# bridge.net
KiCad netlist of a schematic drawn in Altium Designer
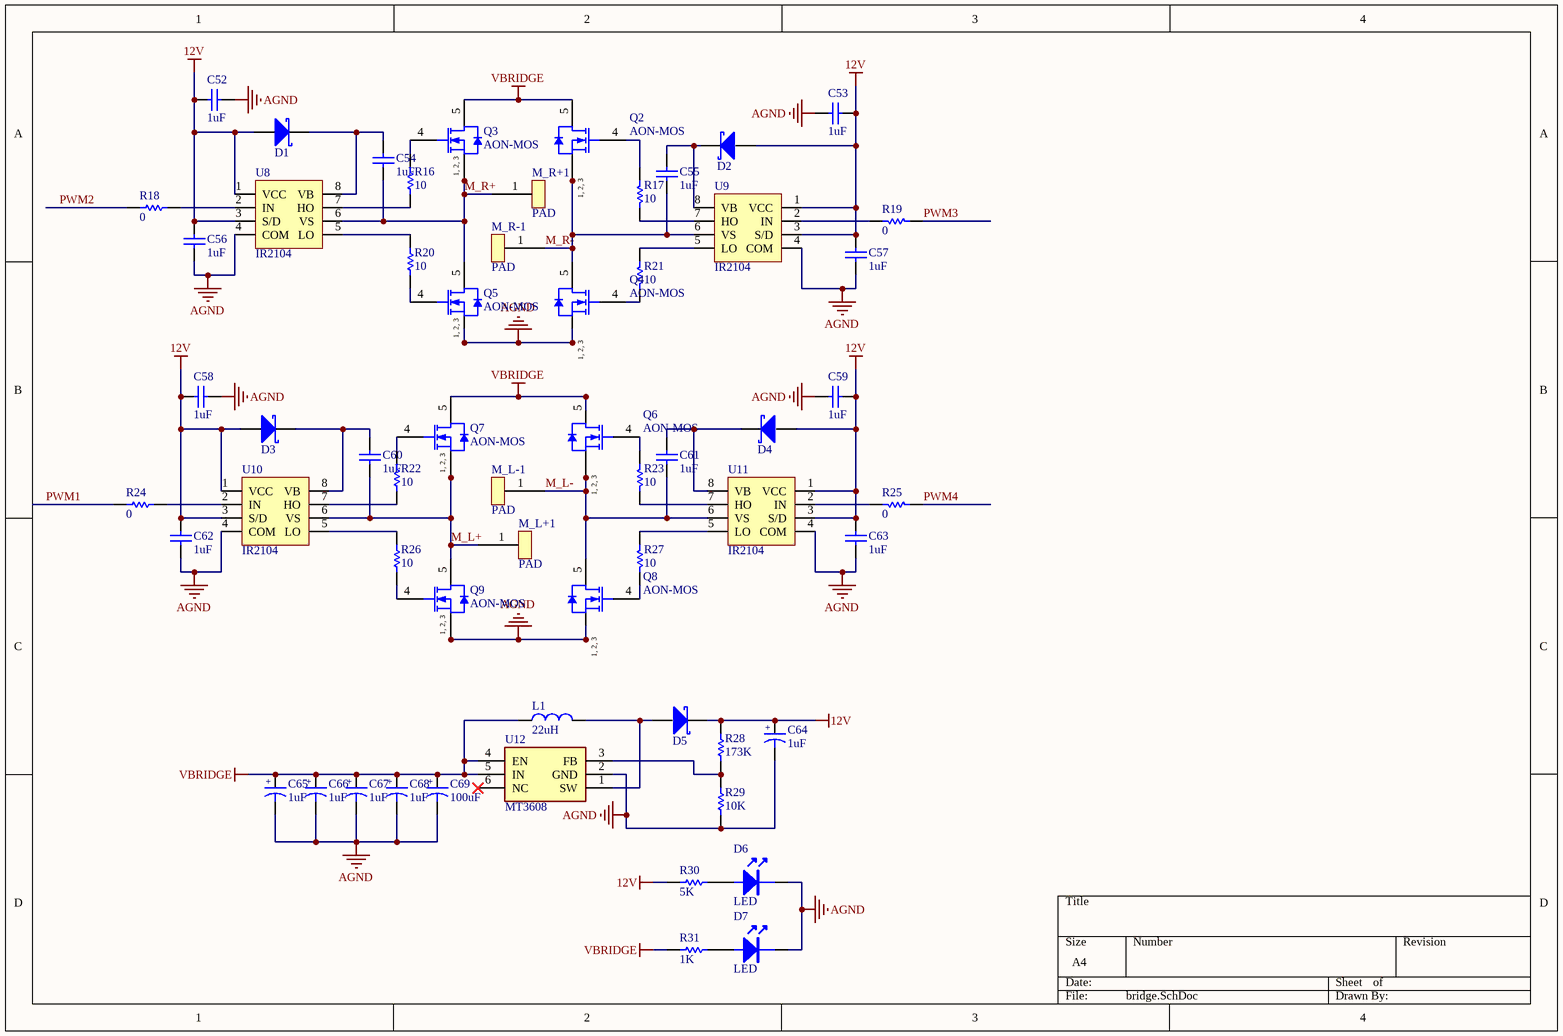
[diagram p0: bridge.SchDoc]

(export (version "E")
  (design (tool "Eeschema 10.0.6"))
  (components
    (comp (ref "C52")
      (value "1uF")
      (footprint "C1210")
      (description "Capacitor")
      (fields (field (name "PUBLISHER") "Altium Limited"))
      (libsource (lib "My Footprint") (part "CAP"))
    )
    (comp (ref "C53")
      (value "1uF")
      (footprint "C1210")
      (description "Capacitor")
      (fields (field (name "PUBLISHER") "Altium Limited"))
      (libsource (lib "My Footprint") (part "CAP"))
    )
    (comp (ref "C54")
      (value "1uF")
      (footprint "0603_C")
      (description "Capacitor")
      (fields (field (name "PUBLISHER") "Altium Limited"))
      (libsource (lib "My Footprint") (part "CAP"))
    )
    (comp (ref "C55")
      (value "1uF")
      (footprint "0603_C")
      (description "Capacitor")
      (fields (field (name "PUBLISHER") "Altium Limited"))
      (libsource (lib "My Footprint") (part "CAP"))
    )
    (comp (ref "C56")
      (value "1uF")
      (footprint "0603_C")
      (description "Capacitor")
      (fields (field (name "PUBLISHER") "Altium Limited"))
      (libsource (lib "My Footprint") (part "CAP"))
    )
    (comp (ref "C57")
      (value "1uF")
      (footprint "0603_C")
      (description "Capacitor")
      (fields (field (name "PUBLISHER") "Altium Limited"))
      (libsource (lib "My Footprint") (part "CAP"))
    )
    (comp (ref "C58")
      (value "1uF")
      (footprint "C1210")
      (description "Capacitor")
      (fields (field (name "PUBLISHER") "Altium Limited"))
      (libsource (lib "My Footprint") (part "CAP"))
    )
    (comp (ref "C59")
      (value "1uF")
      (footprint "C1210")
      (description "Capacitor")
      (fields (field (name "PUBLISHER") "Altium Limited"))
      (libsource (lib "My Footprint") (part "CAP"))
    )
    (comp (ref "C60")
      (value "1uF")
      (footprint "0603_C")
      (description "Capacitor")
      (fields (field (name "PUBLISHER") "Altium Limited"))
      (libsource (lib "My Footprint") (part "CAP"))
    )
    (comp (ref "C61")
      (value "1uF")
      (footprint "0603_C")
      (description "Capacitor")
      (fields (field (name "PUBLISHER") "Altium Limited"))
      (libsource (lib "My Footprint") (part "CAP"))
    )
    (comp (ref "C62")
      (value "1uF")
      (footprint "0603_C")
      (description "Capacitor")
      (fields (field (name "PUBLISHER") "Altium Limited"))
      (libsource (lib "My Footprint") (part "CAP"))
    )
    (comp (ref "C63")
      (value "1uF")
      (footprint "0603_C")
      (description "Capacitor")
      (fields (field (name "PUBLISHER") "Altium Limited"))
      (libsource (lib "My Footprint") (part "CAP"))
    )
    (comp (ref "C64") (value "1uF") (footprint "C6.3X6.3") (libsource (lib "My Footprint") (part "CAP1")))
    (comp (ref "C65") (value "1uF") (footprint "C6.3X6.3") (libsource (lib "My Footprint") (part "CAP1")))
    (comp (ref "C66") (value "1uF") (footprint "C6.3X6.3") (libsource (lib "My Footprint") (part "CAP1")))
    (comp (ref "C67") (value "1uF") (footprint "C6.3X6.3") (libsource (lib "My Footprint") (part "CAP1")))
    (comp (ref "C68") (value "1uF") (footprint "C6.3X6.3") (libsource (lib "My Footprint") (part "CAP1")))
    (comp (ref "C69")
      (value "100uF")
      (footprint "C6.3X6.3")
      (libsource (lib "PCB_Project1") (part "Cap_polar"))
    )
    (comp (ref "D1")
      (value "Diode Schottky")
      (footprint "DO-214AC")
      (libsource (lib "通用驱动") (part "Diode Schottky"))
    )
    (comp (ref "D2")
      (value "Diode Schottky")
      (footprint "DO-214AC")
      (libsource (lib "通用驱动") (part "Diode Schottky"))
    )
    (comp (ref "D3")
      (value "Diode Schottky")
      (footprint "DO-214AC")
      (libsource (lib "通用驱动") (part "Diode Schottky"))
    )
    (comp (ref "D4")
      (value "Diode Schottky")
      (footprint "DO-214AC")
      (libsource (lib "通用驱动") (part "Diode Schottky"))
    )
    (comp (ref "D5")
      (value "Diode Schottky")
      (footprint "DO-214AC")
      (libsource (lib "通用驱动") (part "Diode Schottky"))
    )
    (comp (ref "D6")
      (value "LED")
      (footprint "0603_LED")
      (description "LED 发光二极管")
      (libsource (lib "My Footprint") (part "LED"))
    )
    (comp (ref "D7")
      (value "LED")
      (footprint "0603_LED")
      (description "LED 发光二极管")
      (libsource (lib "My Footprint") (part "LED"))
    )
    (comp (ref "L1")
      (value "22uH")
      (footprint "L 5x5")
      (libsource (lib "My Footprint") (part "L_Inductance"))
    )
    (comp (ref "M_L+1") (value "PAD") (footprint "PAD_BIG") (libsource (lib "My Footprint") (part "PAD")))
    (comp (ref "M_L-1") (value "PAD") (footprint "PAD_BIG") (libsource (lib "") (part "PAD_1")))
    (comp (ref "M_R+1") (value "PAD") (footprint "PAD_BIG") (libsource (lib "My Footprint") (part "PAD")))
    (comp (ref "M_R-1") (value "PAD") (footprint "PAD_BIG") (libsource (lib "") (part "PAD_1")))
    (comp (ref "Q2") (value "AON-MOS") (footprint "so-8") (libsource (lib "My Footprint") (part "N-MOS-so")))
    (comp (ref "Q3") (value "AON-MOS") (footprint "so-8") (libsource (lib "My Footprint") (part "N-MOS-so")))
    (comp (ref "Q4") (value "AON-MOS") (footprint "so-8") (libsource (lib "My Footprint") (part "N-MOS-so")))
    (comp (ref "Q5") (value "AON-MOS") (footprint "so-8") (libsource (lib "My Footprint") (part "N-MOS-so")))
    (comp (ref "Q6") (value "AON-MOS") (footprint "so-8") (libsource (lib "My Footprint") (part "N-MOS-so")))
    (comp (ref "Q7") (value "AON-MOS") (footprint "so-8") (libsource (lib "My Footprint") (part "N-MOS-so")))
    (comp (ref "Q8") (value "AON-MOS") (footprint "so-8") (libsource (lib "My Footprint") (part "N-MOS-so")))
    (comp (ref "Q9") (value "AON-MOS") (footprint "so-8") (libsource (lib "My Footprint") (part "N-MOS-so")))
    (comp (ref "R16")
      (value "10")
      (footprint "0603_R")
      (description "Resistor")
      (fields (field (name "PUBLISHER") "Altium Limited"))
      (libsource (lib "My Footprint") (part "RES"))
    )
    (comp (ref "R17")
      (value "10")
      (footprint "0603_R")
      (description "Resistor")
      (fields (field (name "PUBLISHER") "Altium Limited"))
      (libsource (lib "My Footprint") (part "RES"))
    )
    (comp (ref "R18")
      (value "0")
      (footprint "0603_R")
      (description "Resistor")
      (fields (field (name "PUBLISHER") "Altium Limited"))
      (libsource (lib "My Footprint") (part "RES"))
    )
    (comp (ref "R19")
      (value "0")
      (footprint "0603_R")
      (description "Resistor")
      (fields (field (name "PUBLISHER") "Altium Limited"))
      (libsource (lib "My Footprint") (part "RES"))
    )
    (comp (ref "R20")
      (value "10")
      (footprint "0603_R")
      (description "Resistor")
      (fields (field (name "PUBLISHER") "Altium Limited"))
      (libsource (lib "My Footprint") (part "RES"))
    )
    (comp (ref "R21")
      (value "10")
      (footprint "0603_R")
      (description "Resistor")
      (fields (field (name "PUBLISHER") "Altium Limited"))
      (libsource (lib "My Footprint") (part "RES"))
    )
    (comp (ref "R22")
      (value "10")
      (footprint "0603_R")
      (description "Resistor")
      (fields (field (name "PUBLISHER") "Altium Limited"))
      (libsource (lib "My Footprint") (part "RES"))
    )
    (comp (ref "R23")
      (value "10")
      (footprint "0603_R")
      (description "Resistor")
      (fields (field (name "PUBLISHER") "Altium Limited"))
      (libsource (lib "My Footprint") (part "RES"))
    )
    (comp (ref "R24")
      (value "0")
      (footprint "0603_R")
      (description "Resistor")
      (fields (field (name "PUBLISHER") "Altium Limited"))
      (libsource (lib "My Footprint") (part "RES"))
    )
    (comp (ref "R25")
      (value "0")
      (footprint "0603_R")
      (description "Resistor")
      (fields (field (name "PUBLISHER") "Altium Limited"))
      (libsource (lib "My Footprint") (part "RES"))
    )
    (comp (ref "R26")
      (value "10")
      (footprint "0603_R")
      (description "Resistor")
      (fields (field (name "PUBLISHER") "Altium Limited"))
      (libsource (lib "My Footprint") (part "RES"))
    )
    (comp (ref "R27")
      (value "10")
      (footprint "0603_R")
      (description "Resistor")
      (fields (field (name "PUBLISHER") "Altium Limited"))
      (libsource (lib "My Footprint") (part "RES"))
    )
    (comp (ref "R28")
      (value "173K")
      (footprint "0603_R")
      (description "Resistor")
      (fields (field (name "PUBLISHER") "Altium Limited"))
      (libsource (lib "My Footprint") (part "RES"))
    )
    (comp (ref "R29")
      (value "10K")
      (footprint "0603_R")
      (description "Resistor")
      (fields (field (name "PUBLISHER") "Altium Limited"))
      (libsource (lib "My Footprint") (part "RES"))
    )
    (comp (ref "R30")
      (value "5K")
      (footprint "0603_R")
      (description "Resistor")
      (fields (field (name "PUBLISHER") "Altium Limited"))
      (libsource (lib "My Footprint") (part "RES"))
    )
    (comp (ref "R31")
      (value "1K")
      (footprint "0603_R")
      (description "Resistor")
      (fields (field (name "PUBLISHER") "Altium Limited"))
      (libsource (lib "My Footprint") (part "RES"))
    )
    (comp (ref "U8")
      (value "IR2104")
      (footprint "SOIC-8")
      (description "半桥驱动器")
      (libsource (lib "") (part "IR2104_1"))
    )
    (comp (ref "U9")
      (value "IR2104")
      (footprint "SOIC-8")
      (description "半桥驱动器")
      (libsource (lib "通用驱动") (part "IR2104"))
    )
    (comp (ref "U10")
      (value "IR2104")
      (footprint "SOIC-8")
      (description "半桥驱动器")
      (libsource (lib "") (part "IR2104_1"))
    )
    (comp (ref "U11")
      (value "IR2104")
      (footprint "SOIC-8")
      (description "半桥驱动器")
      (libsource (lib "通用驱动") (part "IR2104"))
    )
    (comp (ref "U12")
      (value "MT3608")
      (footprint "PcbLib_Online:SOT95P280X145-6N")
      (description "Undefined or Miscellaneous")
      (libsource (lib "sch_online") (part "MT3608"))
    )
  )
  (nets
    (net (code "1") (name "/M_L+") (class "Default")
      (node (ref "C60") (pin "1") (pinfunction "1_1") (pintype "passive"))
      (node (ref "M_L+1") (pin "1") (pintype "passive"))
      (node (ref "Q7") (pin "1") (pinfunction "S_1") (pintype "passive"))
      (node (ref "Q7") (pin "2") (pinfunction "S_2") (pintype "passive"))
      (node (ref "Q7") (pin "3") (pinfunction "S_3") (pintype "passive"))
      (node (ref "Q9") (pin "5") (pinfunction "D_5") (pintype "passive"))
      (node (ref "U10") (pin "6") (pinfunction "VS_6") (pintype "passive"))
    )
    (net (code "2") (name "/M_L-") (class "Default")
      (node (ref "C61") (pin "1") (pinfunction "1_1") (pintype "passive"))
      (node (ref "M_L-1") (pin "1") (pintype "passive"))
      (node (ref "Q6") (pin "1") (pinfunction "S_1") (pintype "passive"))
      (node (ref "Q6") (pin "2") (pinfunction "S_2") (pintype "passive"))
      (node (ref "Q6") (pin "3") (pinfunction "S_3") (pintype "passive"))
      (node (ref "Q8") (pin "5") (pinfunction "D_5") (pintype "passive"))
      (node (ref "U11") (pin "6") (pinfunction "VS_6") (pintype "passive"))
    )
    (net (code "3") (name "/M_R+") (class "Default")
      (node (ref "C54") (pin "1") (pinfunction "1_1") (pintype "passive"))
      (node (ref "M_R+1") (pin "1") (pintype "passive"))
      (node (ref "Q3") (pin "1") (pinfunction "S_1") (pintype "passive"))
      (node (ref "Q3") (pin "2") (pinfunction "S_2") (pintype "passive"))
      (node (ref "Q3") (pin "3") (pinfunction "S_3") (pintype "passive"))
      (node (ref "Q5") (pin "5") (pinfunction "D_5") (pintype "passive"))
      (node (ref "U8") (pin "6") (pinfunction "VS_6") (pintype "passive"))
    )
    (net (code "4") (name "/M_R-") (class "Default")
      (node (ref "C55") (pin "1") (pinfunction "1_1") (pintype "passive"))
      (node (ref "M_R-1") (pin "1") (pintype "passive"))
      (node (ref "Q2") (pin "1") (pinfunction "S_1") (pintype "passive"))
      (node (ref "Q2") (pin "2") (pinfunction "S_2") (pintype "passive"))
      (node (ref "Q2") (pin "3") (pinfunction "S_3") (pintype "passive"))
      (node (ref "Q4") (pin "5") (pinfunction "D_5") (pintype "passive"))
      (node (ref "U9") (pin "6") (pinfunction "VS_6") (pintype "passive"))
    )
    (net (code "5") (name "/PWM1") (class "Default")
      (node (ref "R24") (pin "1") (pinfunction "1_1") (pintype "passive"))
    )
    (net (code "6") (name "/PWM2") (class "Default")
      (node (ref "R18") (pin "1") (pinfunction "1_1") (pintype "passive"))
    )
    (net (code "7") (name "/PWM3") (class "Default")
      (node (ref "R19") (pin "1") (pinfunction "1_1") (pintype "passive"))
    )
    (net (code "8") (name "/PWM4") (class "Default")
      (node (ref "R25") (pin "1") (pinfunction "1_1") (pintype "passive"))
    )
    (net (code "9") (name "12V") (class "Default")
      (node (ref "C52") (pin "1") (pinfunction "1_1") (pintype "passive"))
      (node (ref "C53") (pin "2") (pinfunction "2_2") (pintype "passive"))
      (node (ref "C56") (pin "2") (pinfunction "2_2") (pintype "passive"))
      (node (ref "C57") (pin "2") (pinfunction "2_2") (pintype "passive"))
      (node (ref "C58") (pin "1") (pinfunction "1_1") (pintype "passive"))
      (node (ref "C59") (pin "2") (pinfunction "2_2") (pintype "passive"))
      (node (ref "C62") (pin "2") (pinfunction "2_2") (pintype "passive"))
      (node (ref "C63") (pin "2") (pinfunction "2_2") (pintype "passive"))
      (node (ref "C64") (pin "1") (pinfunction "1_1") (pintype "passive"))
      (node (ref "D1") (pin "1") (pinfunction "A_1") (pintype "passive"))
      (node (ref "D2") (pin "1") (pinfunction "A_1") (pintype "passive"))
      (node (ref "D3") (pin "1") (pinfunction "A_1") (pintype "passive"))
      (node (ref "D4") (pin "1") (pinfunction "A_1") (pintype "passive"))
      (node (ref "D5") (pin "2") (pinfunction "K_2") (pintype "passive"))
      (node (ref "R28") (pin "2") (pinfunction "2_2") (pintype "passive"))
      (node (ref "R30") (pin "2") (pinfunction "2_2") (pintype "passive"))
      (node (ref "U10") (pin "1") (pinfunction "VCC_1") (pintype "passive"))
      (node (ref "U10") (pin "3") (pinfunction "S/D_3") (pintype "passive"))
      (node (ref "U11") (pin "1") (pinfunction "VCC_1") (pintype "passive"))
      (node (ref "U11") (pin "3") (pinfunction "S/D_3") (pintype "passive"))
      (node (ref "U8") (pin "1") (pinfunction "VCC_1") (pintype "passive"))
      (node (ref "U8") (pin "3") (pinfunction "S/D_3") (pintype "passive"))
      (node (ref "U9") (pin "1") (pinfunction "VCC_1") (pintype "passive"))
      (node (ref "U9") (pin "3") (pinfunction "S/D_3") (pintype "passive"))
    )
    (net (code "10") (name "AGND") (class "Default")
      (node (ref "C52") (pin "2") (pinfunction "2_2") (pintype "passive"))
      (node (ref "C53") (pin "1") (pinfunction "1_1") (pintype "passive"))
      (node (ref "C56") (pin "1") (pinfunction "1_1") (pintype "passive"))
      (node (ref "C57") (pin "1") (pinfunction "1_1") (pintype "passive"))
      (node (ref "C58") (pin "2") (pinfunction "2_2") (pintype "passive"))
      (node (ref "C59") (pin "1") (pinfunction "1_1") (pintype "passive"))
      (node (ref "C62") (pin "1") (pinfunction "1_1") (pintype "passive"))
      (node (ref "C63") (pin "1") (pinfunction "1_1") (pintype "passive"))
      (node (ref "C64") (pin "2") (pinfunction "2_2") (pintype "passive"))
      (node (ref "C65") (pin "2") (pinfunction "2_2") (pintype "passive"))
      (node (ref "C66") (pin "2") (pinfunction "2_2") (pintype "passive"))
      (node (ref "C67") (pin "2") (pinfunction "2_2") (pintype "passive"))
      (node (ref "C68") (pin "2") (pinfunction "2_2") (pintype "passive"))
      (node (ref "C69") (pin "2") (pinfunction "2_2") (pintype "passive"))
      (node (ref "D6") (pin "2") (pinfunction "K_2") (pintype "passive"))
      (node (ref "D7") (pin "2") (pinfunction "K_2") (pintype "passive"))
      (node (ref "Q4") (pin "1") (pinfunction "S_1") (pintype "passive"))
      (node (ref "Q4") (pin "2") (pinfunction "S_2") (pintype "passive"))
      (node (ref "Q4") (pin "3") (pinfunction "S_3") (pintype "passive"))
      (node (ref "Q5") (pin "1") (pinfunction "S_1") (pintype "passive"))
      (node (ref "Q5") (pin "2") (pinfunction "S_2") (pintype "passive"))
      (node (ref "Q5") (pin "3") (pinfunction "S_3") (pintype "passive"))
      (node (ref "Q8") (pin "1") (pinfunction "S_1") (pintype "passive"))
      (node (ref "Q8") (pin "2") (pinfunction "S_2") (pintype "passive"))
      (node (ref "Q8") (pin "3") (pinfunction "S_3") (pintype "passive"))
      (node (ref "Q9") (pin "1") (pinfunction "S_1") (pintype "passive"))
      (node (ref "Q9") (pin "2") (pinfunction "S_2") (pintype "passive"))
      (node (ref "Q9") (pin "3") (pinfunction "S_3") (pintype "passive"))
      (node (ref "R29") (pin "1") (pinfunction "1_1") (pintype "passive"))
      (node (ref "U10") (pin "4") (pinfunction "COM_4") (pintype "passive"))
      (node (ref "U11") (pin "4") (pinfunction "COM_4") (pintype "passive"))
      (node (ref "U12") (pin "2") (pinfunction "GND_2") (pintype "passive"))
      (node (ref "U8") (pin "4") (pinfunction "COM_4") (pintype "passive"))
      (node (ref "U9") (pin "4") (pinfunction "COM_4") (pintype "passive"))
    )
    (net (code "11") (name "Net-(D1-K)") (class "Default")
      (node (ref "C54") (pin "2") (pinfunction "2_2") (pintype "passive"))
      (node (ref "D1") (pin "2") (pinfunction "K_2") (pintype "passive"))
      (node (ref "U8") (pin "8") (pinfunction "VB_8") (pintype "passive"))
    )
    (net (code "12") (name "Net-(D2-K)") (class "Default")
      (node (ref "C55") (pin "2") (pinfunction "2_2") (pintype "passive"))
      (node (ref "D2") (pin "2") (pinfunction "K_2") (pintype "passive"))
      (node (ref "U9") (pin "8") (pinfunction "VB_8") (pintype "passive"))
    )
    (net (code "13") (name "Net-(D3-K)") (class "Default")
      (node (ref "C60") (pin "2") (pinfunction "2_2") (pintype "passive"))
      (node (ref "D3") (pin "2") (pinfunction "K_2") (pintype "passive"))
      (node (ref "U10") (pin "8") (pinfunction "VB_8") (pintype "passive"))
    )
    (net (code "14") (name "Net-(D4-K)") (class "Default")
      (node (ref "C61") (pin "2") (pinfunction "2_2") (pintype "passive"))
      (node (ref "D4") (pin "2") (pinfunction "K_2") (pintype "passive"))
      (node (ref "U11") (pin "8") (pinfunction "VB_8") (pintype "passive"))
    )
    (net (code "15") (name "Net-(D5-A)") (class "Default")
      (node (ref "D5") (pin "1") (pinfunction "A_1") (pintype "passive"))
      (node (ref "L1") (pin "2") (pinfunction "2_2") (pintype "passive"))
      (node (ref "U12") (pin "1") (pinfunction "SW_1") (pintype "passive"))
    )
    (net (code "16") (name "Net-(D6-A)") (class "Default")
      (node (ref "D6") (pin "1") (pinfunction "A_1") (pintype "passive"))
      (node (ref "R30") (pin "1") (pinfunction "1_1") (pintype "passive"))
    )
    (net (code "17") (name "Net-(D7-A)") (class "Default")
      (node (ref "D7") (pin "1") (pinfunction "A_1") (pintype "passive"))
      (node (ref "R31") (pin "1") (pinfunction "1_1") (pintype "passive"))
    )
    (net (code "18") (name "Net-(Q2-G)") (class "Default")
      (node (ref "Q2") (pin "4") (pinfunction "G_4") (pintype "passive"))
      (node (ref "R17") (pin "2") (pinfunction "2_2") (pintype "passive"))
    )
    (net (code "19") (name "Net-(Q3-G)") (class "Default")
      (node (ref "Q3") (pin "4") (pinfunction "G_4") (pintype "passive"))
      (node (ref "R16") (pin "2") (pinfunction "2_2") (pintype "passive"))
    )
    (net (code "20") (name "Net-(Q4-G)") (class "Default")
      (node (ref "Q4") (pin "4") (pinfunction "G_4") (pintype "passive"))
      (node (ref "R21") (pin "2") (pinfunction "2_2") (pintype "passive"))
    )
    (net (code "21") (name "Net-(Q5-G)") (class "Default")
      (node (ref "Q5") (pin "4") (pinfunction "G_4") (pintype "passive"))
      (node (ref "R20") (pin "2") (pinfunction "2_2") (pintype "passive"))
    )
    (net (code "22") (name "Net-(Q6-G)") (class "Default")
      (node (ref "Q6") (pin "4") (pinfunction "G_4") (pintype "passive"))
      (node (ref "R23") (pin "2") (pinfunction "2_2") (pintype "passive"))
    )
    (net (code "23") (name "Net-(Q7-G)") (class "Default")
      (node (ref "Q7") (pin "4") (pinfunction "G_4") (pintype "passive"))
      (node (ref "R22") (pin "2") (pinfunction "2_2") (pintype "passive"))
    )
    (net (code "24") (name "Net-(Q8-G)") (class "Default")
      (node (ref "Q8") (pin "4") (pinfunction "G_4") (pintype "passive"))
      (node (ref "R27") (pin "2") (pinfunction "2_2") (pintype "passive"))
    )
    (net (code "25") (name "Net-(Q9-G)") (class "Default")
      (node (ref "Q9") (pin "4") (pinfunction "G_4") (pintype "passive"))
      (node (ref "R26") (pin "2") (pinfunction "2_2") (pintype "passive"))
    )
    (net (code "26") (name "Net-(U8-HO)") (class "Default")
      (node (ref "R16") (pin "1") (pinfunction "1_1") (pintype "passive"))
      (node (ref "U8") (pin "7") (pinfunction "HO_7") (pintype "passive"))
    )
    (net (code "27") (name "Net-(U8-IN)") (class "Default")
      (node (ref "R18") (pin "2") (pinfunction "2_2") (pintype "passive"))
      (node (ref "U8") (pin "2") (pinfunction "IN_2") (pintype "passive"))
    )
    (net (code "28") (name "Net-(U8-LO)") (class "Default")
      (node (ref "R20") (pin "1") (pinfunction "1_1") (pintype "passive"))
      (node (ref "U8") (pin "5") (pinfunction "LO_5") (pintype "passive"))
    )
    (net (code "29") (name "Net-(U9-HO)") (class "Default")
      (node (ref "R17") (pin "1") (pinfunction "1_1") (pintype "passive"))
      (node (ref "U9") (pin "7") (pinfunction "HO_7") (pintype "passive"))
    )
    (net (code "30") (name "Net-(U9-IN)") (class "Default")
      (node (ref "R19") (pin "2") (pinfunction "2_2") (pintype "passive"))
      (node (ref "U9") (pin "2") (pinfunction "IN_2") (pintype "passive"))
    )
    (net (code "31") (name "Net-(U9-LO)") (class "Default")
      (node (ref "R21") (pin "1") (pinfunction "1_1") (pintype "passive"))
      (node (ref "U9") (pin "5") (pinfunction "LO_5") (pintype "passive"))
    )
    (net (code "32") (name "Net-(U10-HO)") (class "Default")
      (node (ref "R22") (pin "1") (pinfunction "1_1") (pintype "passive"))
      (node (ref "U10") (pin "7") (pinfunction "HO_7") (pintype "passive"))
    )
    (net (code "33") (name "Net-(U10-IN)") (class "Default")
      (node (ref "R24") (pin "2") (pinfunction "2_2") (pintype "passive"))
      (node (ref "U10") (pin "2") (pinfunction "IN_2") (pintype "passive"))
    )
    (net (code "34") (name "Net-(U10-LO)") (class "Default")
      (node (ref "R26") (pin "1") (pinfunction "1_1") (pintype "passive"))
      (node (ref "U10") (pin "5") (pinfunction "LO_5") (pintype "passive"))
    )
    (net (code "35") (name "Net-(U11-HO)") (class "Default")
      (node (ref "R23") (pin "1") (pinfunction "1_1") (pintype "passive"))
      (node (ref "U11") (pin "7") (pinfunction "HO_7") (pintype "passive"))
    )
    (net (code "36") (name "Net-(U11-IN)") (class "Default")
      (node (ref "R25") (pin "2") (pinfunction "2_2") (pintype "passive"))
      (node (ref "U11") (pin "2") (pinfunction "IN_2") (pintype "passive"))
    )
    (net (code "37") (name "Net-(U11-LO)") (class "Default")
      (node (ref "R27") (pin "1") (pinfunction "1_1") (pintype "passive"))
      (node (ref "U11") (pin "5") (pinfunction "LO_5") (pintype "passive"))
    )
    (net (code "38") (name "Net-(U12-FB)") (class "Default")
      (node (ref "R28") (pin "1") (pinfunction "1_1") (pintype "passive"))
      (node (ref "R29") (pin "2") (pinfunction "2_2") (pintype "passive"))
      (node (ref "U12") (pin "3") (pinfunction "FB_3") (pintype "passive"))
    )
    (net (code "39") (name "VBRIDGE") (class "Default")
      (node (ref "C65") (pin "1") (pinfunction "1_1") (pintype "passive"))
      (node (ref "C66") (pin "1") (pinfunction "1_1") (pintype "passive"))
      (node (ref "C67") (pin "1") (pinfunction "1_1") (pintype "passive"))
      (node (ref "C68") (pin "1") (pinfunction "1_1") (pintype "passive"))
      (node (ref "C69") (pin "1") (pinfunction "1_1") (pintype "passive"))
      (node (ref "L1") (pin "1") (pinfunction "1_1") (pintype "passive"))
      (node (ref "Q2") (pin "5") (pinfunction "D_5") (pintype "passive"))
      (node (ref "Q3") (pin "5") (pinfunction "D_5") (pintype "passive"))
      (node (ref "Q6") (pin "5") (pinfunction "D_5") (pintype "passive"))
      (node (ref "Q7") (pin "5") (pinfunction "D_5") (pintype "passive"))
      (node (ref "R31") (pin "2") (pinfunction "2_2") (pintype "passive"))
      (node (ref "U12") (pin "4") (pinfunction "EN_4") (pintype "passive"))
      (node (ref "U12") (pin "5") (pinfunction "IN_5") (pintype "passive"))
    )
    (net (code "40") (name "unconnected-(U12-NC-Pad6)") (class "Default")
      (node (ref "U12") (pin "6") (pinfunction "NC_6") (pintype "passive+no_connect"))
    )
  )
)
